# design.net
KiCad netlist of a schematic drawn in Altium Designer
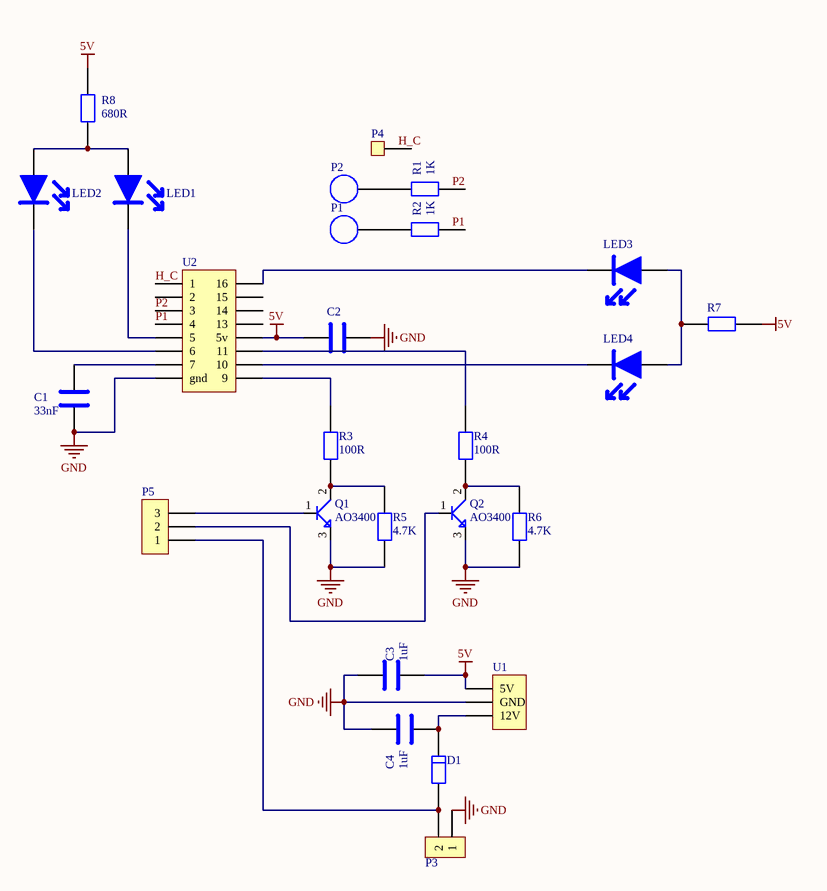
[diagram p0: 双键灯.SchDoc]

(export (version "E")
  (design (tool "Eeschema 10.0.6"))
  (components
    (comp (ref "C1") (value "33nF") (footprint "C0603") (libsource (lib "双键灯") (part "cap")))
    (comp (ref "C2") (value "cap") (footprint "C0603") (libsource (lib "双键灯") (part "cap")))
    (comp (ref "C3") (value "1uF") (footprint "C0603") (libsource (lib "双键灯") (part "cap")))
    (comp (ref "C4") (value "1uF") (footprint "C0603") (libsource (lib "双键灯") (part "cap")))
    (comp (ref "D1") (value "sod") (footprint "SOD123") (libsource (lib "双键灯") (part "sod")))
    (comp (ref "LED1") (value "led") (footprint "3806(020LED)") (libsource (lib "双键灯") (part "led")))
    (comp (ref "LED2") (value "led") (footprint "3806(020LED)") (libsource (lib "双键灯") (part "led")))
    (comp (ref "LED3") (value "led") (footprint "3806(020LED)") (libsource (lib "双键灯") (part "led")))
    (comp (ref "LED4") (value "led") (footprint "3806(020LED)") (libsource (lib "双键灯") (part "led")))
    (comp (ref "P1") (value "T_PAD") (footprint "TOUCH_PAD") (libsource (lib "双键灯") (part "T_PAD")))
    (comp (ref "P2") (value "T_PAD") (footprint "TOUCH_PAD") (libsource (lib "双键灯") (part "T_PAD")))
    (comp (ref "P3") (value "pad2") (footprint "PAD_2 _ab") (libsource (lib "双键灯") (part "pad2")))
    (comp (ref "P4") (value "pad1") (footprint "PAD") (libsource (lib "双键灯") (part "pad1")))
    (comp (ref "P5") (value "pad3") (footprint "PAD*3") (libsource (lib "双键灯") (part "pad3")))
    (comp (ref "Q1") (value "AO3400") (footprint "TO-252") (libsource (lib "双键灯") (part "pnp")))
    (comp (ref "Q2") (value "AO3400") (footprint "TO-252") (libsource (lib "双键灯") (part "pnp")))
    (comp (ref "R1") (value "1K") (footprint "R0603") (libsource (lib "双键灯") (part "res")))
    (comp (ref "R2") (value "1K") (footprint "R0603") (libsource (lib "双键灯") (part "res")))
    (comp (ref "R3") (value "100R") (footprint "R0603") (libsource (lib "双键灯") (part "res")))
    (comp (ref "R4") (value "100R") (footprint "R0603") (libsource (lib "双键灯") (part "res")))
    (comp (ref "R5") (value "4.7K") (footprint "R0603") (libsource (lib "双键灯") (part "res")))
    (comp (ref "R6") (value "4.7K") (footprint "R0603") (libsource (lib "双键灯") (part "res")))
    (comp (ref "R7") (value "680R") (footprint "R0603") (libsource (lib "双键灯") (part "res")))
    (comp (ref "R8") (value "680R") (footprint "R0603") (libsource (lib "双键灯") (part "res")))
    (comp (ref "U1") (value "u2") (footprint "SOT-89") (libsource (lib "双键灯") (part "u2")))
    (comp (ref "U2") (value "u") (footprint "SOP16") (libsource (lib "双键灯") (part "u")))
  )
  (nets
    (net (code "1") (name "/H_C") (class "Default")
      (node (ref "U2") (pin "1") (pinfunction "1_1") (pintype "passive"))
    )
    (net (code "2") (name "/P1") (class "Default")
      (node (ref "U2") (pin "4") (pinfunction "4_4") (pintype "passive"))
    )
    (net (code "3") (name "/P2") (class "Default")
      (node (ref "U2") (pin "3") (pinfunction "3_3") (pintype "passive"))
    )
    (net (code "4") (name "5V") (class "Default")
      (node (ref "C2") (pin "1") (pinfunction "1_1") (pintype "passive"))
      (node (ref "C3") (pin "2") (pinfunction "2_2") (pintype "passive"))
      (node (ref "R7") (pin "1") (pinfunction "1_1") (pintype "passive"))
      (node (ref "R8") (pin "1") (pinfunction "1_1") (pintype "passive"))
      (node (ref "U1") (pin "1") (pinfunction "5V_1") (pintype "passive"))
      (node (ref "U2") (pin "12") (pinfunction "5v_12") (pintype "passive"))
    )
    (net (code "5") (name "GND") (class "Default")
      (node (ref "C1") (pin "1") (pinfunction "1_1") (pintype "passive"))
      (node (ref "C2") (pin "2") (pinfunction "2_2") (pintype "passive"))
      (node (ref "C3") (pin "1") (pinfunction "1_1") (pintype "passive"))
      (node (ref "C4") (pin "1") (pinfunction "1_1") (pintype "passive"))
      (node (ref "P3") (pin "1") (pinfunction "1_1") (pintype "passive"))
      (node (ref "Q1") (pin "3") (pinfunction "3_3") (pintype "passive"))
      (node (ref "Q2") (pin "3") (pinfunction "3_3") (pintype "passive"))
      (node (ref "R5") (pin "1") (pinfunction "1_1") (pintype "passive"))
      (node (ref "R6") (pin "1") (pinfunction "1_1") (pintype "passive"))
      (node (ref "U1") (pin "2") (pinfunction "GND_2") (pintype "passive"))
      (node (ref "U2") (pin "8") (pinfunction "gnd_8") (pintype "passive"))
    )
    (net (code "6") (name "Net-(C1-Pad2)") (class "Default")
      (node (ref "C1") (pin "2") (pinfunction "2_2") (pintype "passive"))
      (node (ref "U2") (pin "7") (pinfunction "7_7") (pintype "passive"))
    )
    (net (code "7") (name "Net-(D1-Pad1)") (class "Default")
      (node (ref "D1") (pin "1") (pinfunction "1_1") (pintype "passive"))
      (node (ref "P3") (pin "2") (pinfunction "2_2") (pintype "passive"))
      (node (ref "P5") (pin "1") (pinfunction "1_1") (pintype "passive"))
    )
    (net (code "8") (name "Net-(LED1-PadA)") (class "Default")
      (node (ref "LED1") (pin "A") (pinfunction "A_A") (pintype "passive"))
      (node (ref "LED2") (pin "A") (pinfunction "A_A") (pintype "passive"))
      (node (ref "R8") (pin "2") (pinfunction "2_2") (pintype "passive"))
    )
    (net (code "9") (name "Net-(LED1-PadK)") (class "Default")
      (node (ref "LED1") (pin "K") (pinfunction "K_K") (pintype "passive"))
      (node (ref "U2") (pin "5") (pinfunction "5_5") (pintype "passive"))
    )
    (net (code "10") (name "Net-(LED2-PadK)") (class "Default")
      (node (ref "LED2") (pin "K") (pinfunction "K_K") (pintype "passive"))
      (node (ref "U2") (pin "6") (pinfunction "6_6") (pintype "passive"))
    )
    (net (code "11") (name "Net-(LED3-PadA)") (class "Default")
      (node (ref "LED3") (pin "A") (pinfunction "A_A") (pintype "passive"))
      (node (ref "LED4") (pin "A") (pinfunction "A_A") (pintype "passive"))
      (node (ref "R7") (pin "2") (pinfunction "2_2") (pintype "passive"))
    )
    (net (code "12") (name "Net-(LED3-PadK)") (class "Default")
      (node (ref "LED3") (pin "K") (pinfunction "K_K") (pintype "passive"))
      (node (ref "U2") (pin "16") (pinfunction "16_16") (pintype "passive"))
    )
    (net (code "13") (name "Net-(LED4-PadK)") (class "Default")
      (node (ref "LED4") (pin "K") (pinfunction "K_K") (pintype "passive"))
      (node (ref "U2") (pin "10") (pinfunction "10_10") (pintype "passive"))
    )
    (net (code "14") (name "Net-(P1-Pad4)") (class "Default")
      (node (ref "P1") (pin "4") (pinfunction "4_4") (pintype "passive"))
      (node (ref "R2") (pin "2") (pinfunction "2_2") (pintype "passive"))
    )
    (net (code "15") (name "Net-(P2-Pad4)") (class "Default")
      (node (ref "P2") (pin "4") (pinfunction "4_4") (pintype "passive"))
      (node (ref "R1") (pin "2") (pinfunction "2_2") (pintype "passive"))
    )
    (net (code "16") (name "Net-(P5-Pad2)") (class "Default")
      (node (ref "P5") (pin "2") (pinfunction "2_2") (pintype "passive"))
      (node (ref "Q2") (pin "1") (pinfunction "1_1") (pintype "passive"))
    )
    (net (code "17") (name "Net-(P5-Pad3)") (class "Default")
      (node (ref "P5") (pin "3") (pinfunction "3_3") (pintype "passive"))
      (node (ref "Q1") (pin "1") (pinfunction "1_1") (pintype "passive"))
    )
    (net (code "18") (name "Net-(Q1-Pad2)") (class "Default")
      (node (ref "Q1") (pin "2") (pinfunction "2_2") (pintype "passive"))
      (node (ref "R3") (pin "1") (pinfunction "1_1") (pintype "passive"))
      (node (ref "R5") (pin "2") (pinfunction "2_2") (pintype "passive"))
    )
    (net (code "19") (name "Net-(Q2-Pad2)") (class "Default")
      (node (ref "Q2") (pin "2") (pinfunction "2_2") (pintype "passive"))
      (node (ref "R4") (pin "1") (pinfunction "1_1") (pintype "passive"))
      (node (ref "R6") (pin "2") (pinfunction "2_2") (pintype "passive"))
    )
    (net (code "20") (name "Net-(R3-Pad2)") (class "Default")
      (node (ref "R3") (pin "2") (pinfunction "2_2") (pintype "passive"))
      (node (ref "U2") (pin "9") (pinfunction "9_9") (pintype "passive"))
    )
    (net (code "21") (name "Net-(R4-Pad2)") (class "Default")
      (node (ref "R4") (pin "2") (pinfunction "2_2") (pintype "passive"))
      (node (ref "U2") (pin "11") (pinfunction "11_11") (pintype "passive"))
    )
    (net (code "22") (name "Net-(U1-12V)") (class "Default")
      (node (ref "C4") (pin "2") (pinfunction "2_2") (pintype "passive"))
      (node (ref "D1") (pin "2") (pinfunction "2_2") (pintype "passive"))
      (node (ref "U1") (pin "3") (pinfunction "12V_3") (pintype "passive"))
    )
    (net (code "23") (name "unconnected-(P4-Pad1)") (class "Default")
      (node (ref "P4") (pin "1") (pinfunction "1_1") (pintype "passive"))
    )
    (net (code "24") (name "unconnected-(R1-Pad1)") (class "Default")
      (node (ref "R1") (pin "1") (pinfunction "1_1") (pintype "passive"))
    )
    (net (code "25") (name "unconnected-(R2-Pad1)") (class "Default")
      (node (ref "R2") (pin "1") (pinfunction "1_1") (pintype "passive"))
    )
    (net (code "26") (name "unconnected-(U2-Pad2)") (class "Default")
      (node (ref "U2") (pin "2") (pinfunction "2_2") (pintype "passive"))
    )
    (net (code "27") (name "unconnected-(U2-Pad13)") (class "Default")
      (node (ref "U2") (pin "13") (pinfunction "13_13") (pintype "passive"))
    )
    (net (code "28") (name "unconnected-(U2-Pad14)") (class "Default")
      (node (ref "U2") (pin "14") (pinfunction "14_14") (pintype "passive"))
    )
    (net (code "29") (name "unconnected-(U2-Pad15)") (class "Default")
      (node (ref "U2") (pin "15") (pinfunction "15_15") (pintype "passive"))
    )
  )
)
